# versterker_R.net
KiCad netlist of a schematic drawn in Altium Designer
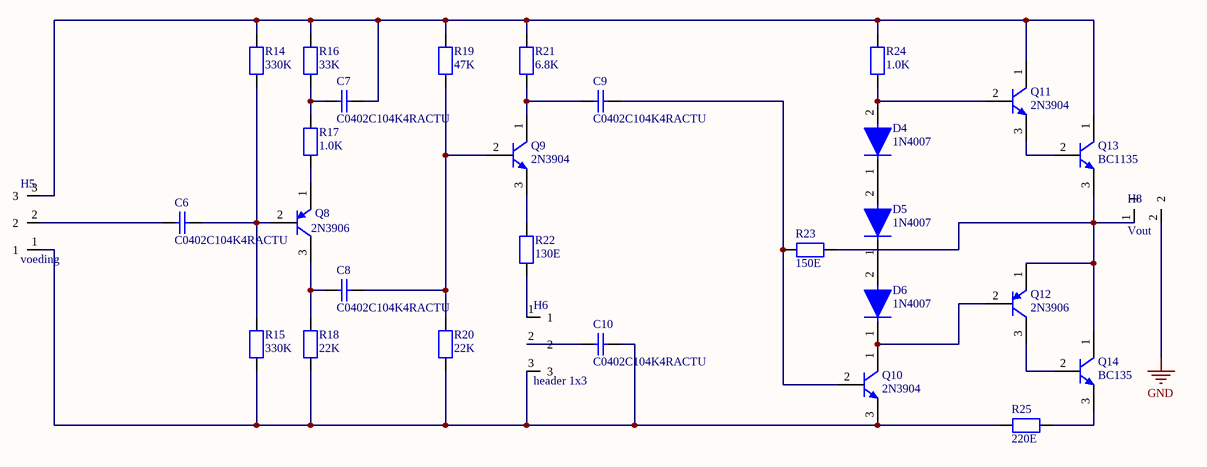
[diagram p0: versterker_R.SchDoc]

(export (version "E")
  (design (tool "Eeschema 10.0.6"))
  (components
    (comp (ref "C6")
      (value "C0402C104K4RACTU")
      (footprint "capacitor SMD")
      (fields (field (name "MANUFACTURER") "Kemet"))
      (libsource (lib "basisSchematicLibrary") (part "capacitor smd"))
    )
    (comp (ref "C7")
      (value "C0402C104K4RACTU")
      (footprint "capacitor SMD")
      (fields (field (name "MANUFACTURER") "Kemet"))
      (libsource (lib "basisSchematicLibrary") (part "capacitor smd"))
    )
    (comp (ref "C8")
      (value "C0402C104K4RACTU")
      (footprint "capacitor SMD")
      (fields (field (name "MANUFACTURER") "Kemet"))
      (libsource (lib "basisSchematicLibrary") (part "capacitor smd"))
    )
    (comp (ref "C9")
      (value "C0402C104K4RACTU")
      (footprint "capacitor SMD")
      (fields (field (name "MANUFACTURER") "Kemet"))
      (libsource (lib "basisSchematicLibrary") (part "capacitor smd"))
    )
    (comp (ref "C10")
      (value "C0402C104K4RACTU")
      (footprint "capacitor SMD")
      (fields (field (name "MANUFACTURER") "Kemet"))
      (libsource (lib "basisSchematicLibrary") (part "capacitor smd"))
    )
    (comp (ref "D4")
      (value "1N4007")
      (footprint "diode")
      (description "Rectifier diode 1000 V 1 A DO-41, ,")
      (fields
        (field (name "MANUFACTURER") "Diotec")
        (field (name "OCTOPART") "https://octopart.com/1n4007-diotec-4040411")
      )
      (libsource (lib "basisSchematicLibrary") (part "diode"))
    )
    (comp (ref "D5")
      (value "1N4007")
      (footprint "diode")
      (description "Rectifier diode 1000 V 1 A DO-41, ,")
      (fields
        (field (name "MANUFACTURER") "Diotec")
        (field (name "OCTOPART") "https://octopart.com/1n4007-diotec-4040411")
      )
      (libsource (lib "basisSchematicLibrary") (part "diode"))
    )
    (comp (ref "D6")
      (value "1N4007")
      (footprint "diode")
      (description "Rectifier diode 1000 V 1 A DO-41, ,")
      (fields
        (field (name "MANUFACTURER") "Diotec")
        (field (name "OCTOPART") "https://octopart.com/1n4007-diotec-4040411")
      )
      (libsource (lib "basisSchematicLibrary") (part "diode"))
    )
    (comp (ref "H5")
      (value "voeding")
      (footprint "header 1x3")
      (libsource (lib "headerSchematicLibrary") (part "header 1x3"))
    )
    (comp (ref "H6")
      (value "header 1x3")
      (footprint "header 1x3")
      (libsource (lib "headerSchematicLibrary") (part "header 1x3"))
    )
    (comp (ref "H8")
      (value "Vout")
      (footprint "header 1x2")
      (libsource (lib "headerSchematicLibrary") (part "header 1x2"))
    )
    (comp (ref "Q8")
      (value "2N3906")
      (footprint "transistor")
      (description "Amplifier Transistor, NPN Silicon, 3-Pin TO-92, Bulk Box")
      (fields (field (name "MANUFACTURER") "On Semiconductor") (field (name "PARTNUMBER") "BC547B"))
      (libsource (lib "basisSchematicLibrary") (part "pnp transistor"))
    )
    (comp (ref "Q9")
      (value "2N3904")
      (footprint "transistor")
      (description "Amplifier Transistor, NPN Silicon, 3-Pin TO-92, Bulk Box")
      (fields (field (name "MANUFACTURER") "On Semiconductor") (field (name "PARTNUMBER") "BC547B"))
      (libsource (lib "basisSchematicLibrary") (part "npn transistor"))
    )
    (comp (ref "Q10")
      (value "2N3904")
      (footprint "transistor")
      (description "Amplifier Transistor, NPN Silicon, 3-Pin TO-92, Bulk Box")
      (fields (field (name "MANUFACTURER") "On Semiconductor") (field (name "PARTNUMBER") "BC547B"))
      (libsource (lib "basisSchematicLibrary") (part "npn transistor"))
    )
    (comp (ref "Q11")
      (value "2N3904")
      (footprint "transistor")
      (description "Amplifier Transistor, NPN Silicon, 3-Pin TO-92, Bulk Box")
      (fields (field (name "MANUFACTURER") "On Semiconductor") (field (name "PARTNUMBER") "BC547B"))
      (libsource (lib "basisSchematicLibrary") (part "npn transistor"))
    )
    (comp (ref "Q12")
      (value "2N3906")
      (footprint "transistor")
      (description "Amplifier Transistor, NPN Silicon, 3-Pin TO-92, Bulk Box")
      (fields (field (name "MANUFACTURER") "On Semiconductor") (field (name "PARTNUMBER") "BC547B"))
      (libsource (lib "basisSchematicLibrary") (part "pnp transistor"))
    )
    (comp (ref "Q13")
      (value "BC1135")
      (footprint "transistor")
      (description "Amplifier Transistor, NPN Silicon, 3-Pin TO-92, Bulk Box")
      (fields (field (name "MANUFACTURER") "On Semiconductor") (field (name "PARTNUMBER") "BC547B"))
      (libsource (lib "basisSchematicLibrary") (part "npn transistor"))
    )
    (comp (ref "Q14")
      (value "BC135")
      (footprint "transistor")
      (description "Amplifier Transistor, NPN Silicon, 3-Pin TO-92, Bulk Box")
      (fields (field (name "MANUFACTURER") "On Semiconductor") (field (name "PARTNUMBER") "BC547B"))
      (libsource (lib "basisSchematicLibrary") (part "npn transistor"))
    )
    (comp (ref "R14")
      (value "330K")
      (footprint "resistor smd")
      (fields (field (name "MANUFACTURER") "Vishay Dale") (field (name "PART NUMBER") "CRCW08050000Z0EA"))
      (libsource (lib "basisSchematicLibrary") (part "resistor smd"))
    )
    (comp (ref "R15")
      (value "330K")
      (footprint "resistor smd")
      (fields (field (name "MANUFACTURER") "Vishay Dale") (field (name "PART NUMBER") "CRCW08050000Z0EA"))
      (libsource (lib "basisSchematicLibrary") (part "resistor smd"))
    )
    (comp (ref "R16")
      (value "33K")
      (footprint "resistor smd")
      (fields (field (name "MANUFACTURER") "Vishay Dale") (field (name "PART NUMBER") "CRCW08050000Z0EA"))
      (libsource (lib "basisSchematicLibrary") (part "resistor smd"))
    )
    (comp (ref "R17")
      (value "1.0K")
      (footprint "resistor smd")
      (fields (field (name "MANUFACTURER") "Vishay Dale") (field (name "PART NUMBER") "CRCW08050000Z0EA"))
      (libsource (lib "basisSchematicLibrary") (part "resistor smd"))
    )
    (comp (ref "R18")
      (value "22K")
      (footprint "resistor smd")
      (fields (field (name "MANUFACTURER") "Vishay Dale") (field (name "PART NUMBER") "CRCW08050000Z0EA"))
      (libsource (lib "basisSchematicLibrary") (part "resistor smd"))
    )
    (comp (ref "R19")
      (value "47K")
      (footprint "resistor smd")
      (fields (field (name "MANUFACTURER") "Vishay Dale") (field (name "PART NUMBER") "CRCW08050000Z0EA"))
      (libsource (lib "basisSchematicLibrary") (part "resistor smd"))
    )
    (comp (ref "R20")
      (value "22K")
      (footprint "resistor smd")
      (fields (field (name "MANUFACTURER") "Vishay Dale") (field (name "PART NUMBER") "CRCW08050000Z0EA"))
      (libsource (lib "basisSchematicLibrary") (part "resistor smd"))
    )
    (comp (ref "R21")
      (value "6.8K")
      (footprint "resistor smd")
      (fields (field (name "MANUFACTURER") "Vishay Dale") (field (name "PART NUMBER") "CRCW08050000Z0EA"))
      (libsource (lib "basisSchematicLibrary") (part "resistor smd"))
    )
    (comp (ref "R22")
      (value "130E")
      (footprint "resistor smd")
      (fields (field (name "MANUFACTURER") "Vishay Dale") (field (name "PART NUMBER") "CRCW08050000Z0EA"))
      (libsource (lib "basisSchematicLibrary") (part "resistor smd"))
    )
    (comp (ref "R23")
      (value "150E")
      (footprint "resistor smd")
      (fields (field (name "MANUFACTURER") "Vishay Dale") (field (name "PART NUMBER") "CRCW08050000Z0EA"))
      (libsource (lib "basisSchematicLibrary") (part "resistor smd"))
    )
    (comp (ref "R24")
      (value "1.0K")
      (footprint "resistor smd")
      (fields (field (name "MANUFACTURER") "Vishay Dale") (field (name "PART NUMBER") "CRCW08050000Z0EA"))
      (libsource (lib "basisSchematicLibrary") (part "resistor smd"))
    )
    (comp (ref "R25")
      (value "220E")
      (footprint "resistor smd")
      (fields (field (name "MANUFACTURER") "Vishay Dale") (field (name "PART NUMBER") "CRCW08050000Z0EA"))
      (libsource (lib "basisSchematicLibrary") (part "resistor smd"))
    )
  )
  (nets
    (net (code "1") (name "GND") (class "Default")
      (node (ref "H8") (pin "2") (pinfunction "2_2") (pintype "passive"))
    )
    (net (code "2") (name "Net-(C6-Pad1)") (class "Default")
      (node (ref "C6") (pin "1") (pinfunction "1_1") (pintype "passive"))
      (node (ref "H5") (pin "2") (pinfunction "2_2") (pintype "passive"))
    )
    (net (code "3") (name "Net-(C7-Pad1)") (class "Default")
      (node (ref "C7") (pin "1") (pinfunction "1_1") (pintype "passive"))
      (node (ref "R16") (pin "1") (pinfunction "1_1") (pintype "passive"))
      (node (ref "R17") (pin "2") (pinfunction "2_2") (pintype "passive"))
    )
    (net (code "4") (name "Net-(C10-Pad1)") (class "Default")
      (node (ref "C10") (pin "1") (pinfunction "1_1") (pintype "passive"))
      (node (ref "H6") (pin "2") (pinfunction "2_2") (pintype "passive"))
    )
    (net (code "5") (name "Net-(D4-A)") (class "Default")
      (node (ref "D4") (pin "2") (pinfunction "A_2") (pintype "passive"))
      (node (ref "Q11") (pin "2") (pinfunction "B_2") (pintype "passive"))
      (node (ref "R24") (pin "1") (pinfunction "1_1") (pintype "passive"))
    )
    (net (code "6") (name "Net-(D4-C)") (class "Default")
      (node (ref "D4") (pin "1") (pinfunction "C_1") (pintype "passive"))
      (node (ref "D5") (pin "2") (pinfunction "A_2") (pintype "passive"))
    )
    (net (code "7") (name "Net-(D5-C)") (class "Default")
      (node (ref "D5") (pin "1") (pinfunction "C_1") (pintype "passive"))
      (node (ref "D6") (pin "2") (pinfunction "A_2") (pintype "passive"))
    )
    (net (code "8") (name "Net-(D6-C)") (class "Default")
      (node (ref "D6") (pin "1") (pinfunction "C_1") (pintype "passive"))
      (node (ref "Q10") (pin "1") (pinfunction "C_1") (pintype "passive"))
      (node (ref "Q12") (pin "2") (pinfunction "B_2") (pintype "passive"))
    )
    (net (code "9") (name "Net-(H6-Pad1)") (class "Default")
      (node (ref "H6") (pin "1") (pinfunction "1_1") (pintype "passive"))
      (node (ref "R22") (pin "1") (pinfunction "1_1") (pintype "passive"))
    )
    (net (code "10") (name "Net-(Q8-B)") (class "Default")
      (node (ref "C6") (pin "2") (pinfunction "2_2") (pintype "passive"))
      (node (ref "Q8") (pin "2") (pinfunction "B_2") (pintype "passive"))
      (node (ref "R14") (pin "1") (pinfunction "1_1") (pintype "passive"))
      (node (ref "R15") (pin "2") (pinfunction "2_2") (pintype "passive"))
    )
    (net (code "11") (name "Net-(Q8-C)") (class "Default")
      (node (ref "Q8") (pin "1") (pinfunction "C_1") (pintype "passive"))
      (node (ref "R17") (pin "1") (pinfunction "1_1") (pintype "passive"))
    )
    (net (code "12") (name "Net-(Q8-E)") (class "Default")
      (node (ref "C8") (pin "1") (pinfunction "1_1") (pintype "passive"))
      (node (ref "Q8") (pin "3") (pinfunction "E_3") (pintype "passive"))
      (node (ref "R18") (pin "2") (pinfunction "2_2") (pintype "passive"))
    )
    (net (code "13") (name "Net-(Q9-B)") (class "Default")
      (node (ref "C8") (pin "2") (pinfunction "2_2") (pintype "passive"))
      (node (ref "Q9") (pin "2") (pinfunction "B_2") (pintype "passive"))
      (node (ref "R19") (pin "1") (pinfunction "1_1") (pintype "passive"))
      (node (ref "R20") (pin "2") (pinfunction "2_2") (pintype "passive"))
    )
    (net (code "14") (name "Net-(Q9-C)") (class "Default")
      (node (ref "C9") (pin "1") (pinfunction "1_1") (pintype "passive"))
      (node (ref "Q9") (pin "1") (pinfunction "C_1") (pintype "passive"))
      (node (ref "R21") (pin "1") (pinfunction "1_1") (pintype "passive"))
    )
    (net (code "15") (name "Net-(Q9-E)") (class "Default")
      (node (ref "Q9") (pin "3") (pinfunction "E_3") (pintype "passive"))
      (node (ref "R22") (pin "2") (pinfunction "2_2") (pintype "passive"))
    )
    (net (code "16") (name "Net-(Q10-B)") (class "Default")
      (node (ref "C9") (pin "2") (pinfunction "2_2") (pintype "passive"))
      (node (ref "Q10") (pin "2") (pinfunction "B_2") (pintype "passive"))
      (node (ref "R23") (pin "1") (pinfunction "1_1") (pintype "passive"))
    )
    (net (code "17") (name "Net-(Q10-E)") (class "Default")
      (node (ref "C10") (pin "2") (pinfunction "2_2") (pintype "passive"))
      (node (ref "H5") (pin "1") (pinfunction "1_1") (pintype "passive"))
      (node (ref "H6") (pin "3") (pinfunction "3_3") (pintype "passive"))
      (node (ref "Q10") (pin "3") (pinfunction "E_3") (pintype "passive"))
      (node (ref "R15") (pin "1") (pinfunction "1_1") (pintype "passive"))
      (node (ref "R18") (pin "1") (pinfunction "1_1") (pintype "passive"))
      (node (ref "R20") (pin "1") (pinfunction "1_1") (pintype "passive"))
      (node (ref "R25") (pin "1") (pinfunction "1_1") (pintype "passive"))
    )
    (net (code "18") (name "Net-(Q11-C)") (class "Default")
      (node (ref "C7") (pin "2") (pinfunction "2_2") (pintype "passive"))
      (node (ref "H5") (pin "3") (pinfunction "3_3") (pintype "passive"))
      (node (ref "Q11") (pin "1") (pinfunction "C_1") (pintype "passive"))
      (node (ref "Q13") (pin "1") (pinfunction "C_1") (pintype "passive"))
      (node (ref "R14") (pin "2") (pinfunction "2_2") (pintype "passive"))
      (node (ref "R16") (pin "2") (pinfunction "2_2") (pintype "passive"))
      (node (ref "R19") (pin "2") (pinfunction "2_2") (pintype "passive"))
      (node (ref "R21") (pin "2") (pinfunction "2_2") (pintype "passive"))
      (node (ref "R24") (pin "2") (pinfunction "2_2") (pintype "passive"))
    )
    (net (code "19") (name "Net-(Q11-E)") (class "Default")
      (node (ref "Q11") (pin "3") (pinfunction "E_3") (pintype "passive"))
      (node (ref "Q13") (pin "2") (pinfunction "B_2") (pintype "passive"))
    )
    (net (code "20") (name "Net-(Q12-C)") (class "Default")
      (node (ref "H8") (pin "1") (pinfunction "1_1") (pintype "passive"))
      (node (ref "Q12") (pin "1") (pinfunction "C_1") (pintype "passive"))
      (node (ref "Q13") (pin "3") (pinfunction "E_3") (pintype "passive"))
      (node (ref "Q14") (pin "1") (pinfunction "C_1") (pintype "passive"))
      (node (ref "R23") (pin "2") (pinfunction "2_2") (pintype "passive"))
    )
    (net (code "21") (name "Net-(Q12-E)") (class "Default")
      (node (ref "Q12") (pin "3") (pinfunction "E_3") (pintype "passive"))
      (node (ref "Q14") (pin "2") (pinfunction "B_2") (pintype "passive"))
    )
    (net (code "22") (name "Net-(Q14-E)") (class "Default")
      (node (ref "Q14") (pin "3") (pinfunction "E_3") (pintype "passive"))
      (node (ref "R25") (pin "2") (pinfunction "2_2") (pintype "passive"))
    )
  )
)
